# Yamper.net
KiCad netlist of a schematic drawn in Altium Designer
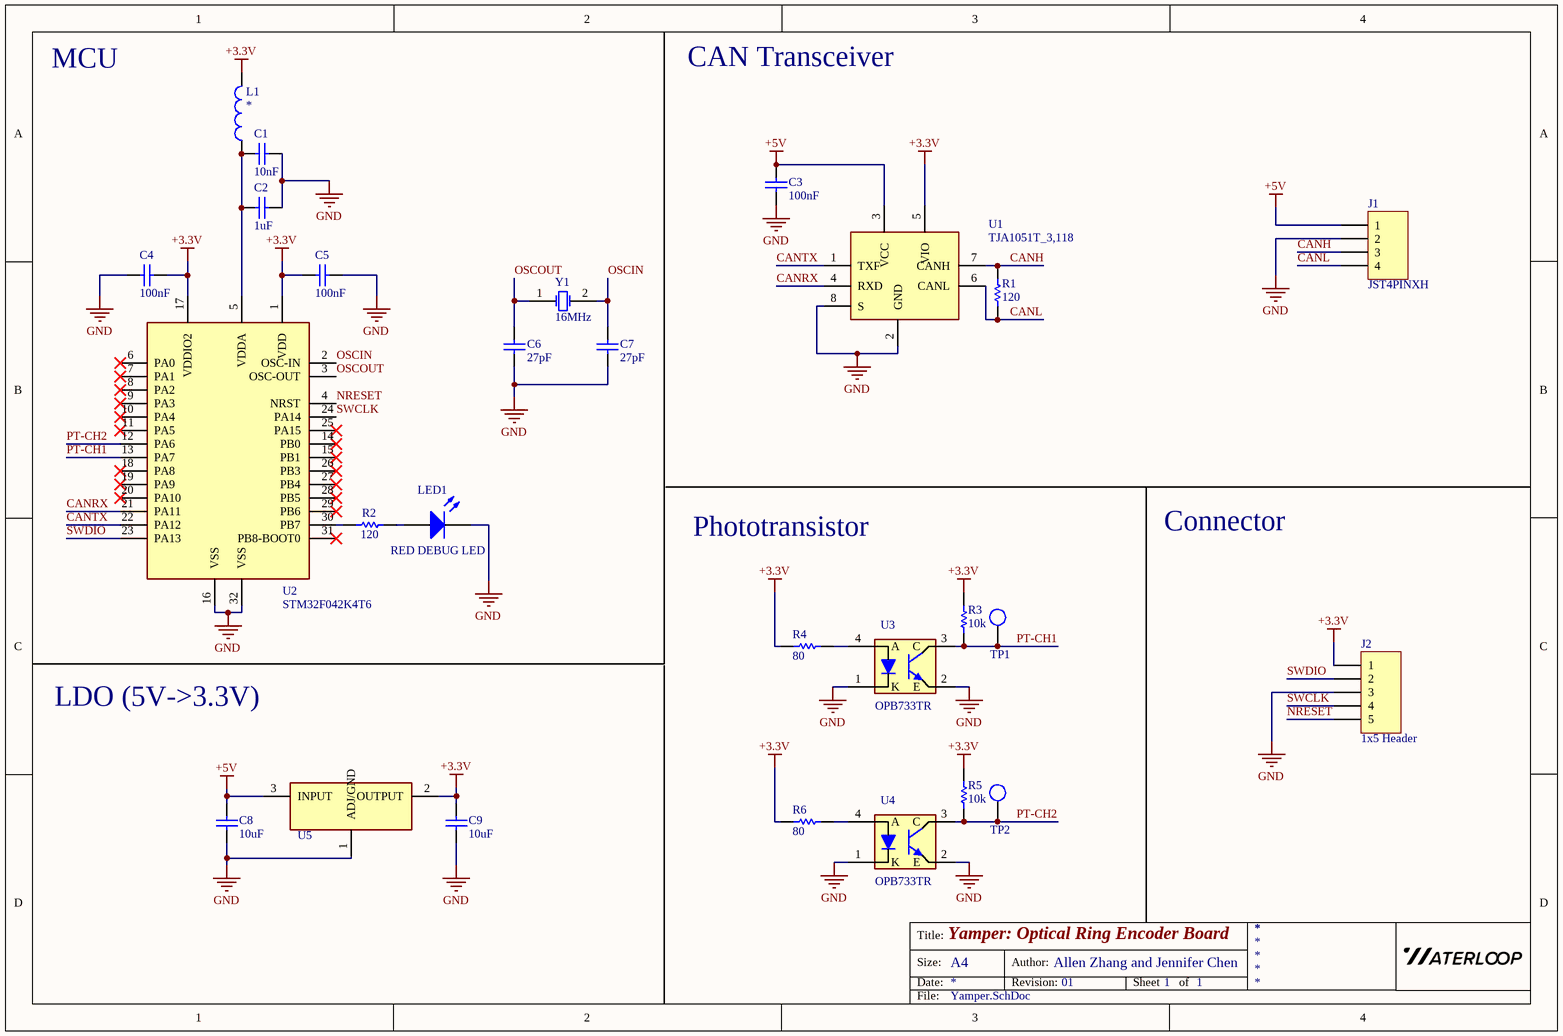
[diagram p0: Yamper.SchDoc]

(export (version "E")
  (design (tool "Eeschema 10.0.6"))
  (components
    (comp (ref "C1")
      (value "10nF")
      (footprint "0805 - Capacitor")
      (description "Nonpolarized Capacitor")
      (fields (field (name "Comment") "Capacitor - Nonpolarized"))
      (libsource (lib "General") (part "Capacitor - Nonpolarized"))
    )
    (comp (ref "C2")
      (value "1uF")
      (footprint "0805 - Capacitor")
      (description "Nonpolarized Capacitor")
      (fields (field (name "Comment") "Capacitor - Nonpolarized"))
      (libsource (lib "General") (part "Capacitor - Nonpolarized"))
    )
    (comp (ref "C3")
      (value "100nF")
      (footprint "0805 - Capacitor")
      (description "Nonpolarized Capacitor")
      (fields (field (name "Comment") "Capacitor - Nonpolarized"))
      (libsource (lib "General") (part "Capacitor - Nonpolarized"))
    )
    (comp (ref "C4")
      (value "100nF")
      (footprint "0805 - Capacitor")
      (description "Nonpolarized Capacitor")
      (fields (field (name "Comment") "Capacitor - Nonpolarized"))
      (libsource (lib "General") (part "Capacitor - Nonpolarized"))
    )
    (comp (ref "C5")
      (value "100nF")
      (footprint "0805 - Capacitor")
      (description "Nonpolarized Capacitor")
      (fields (field (name "Comment") "Capacitor - Nonpolarized"))
      (libsource (lib "General") (part "Capacitor - Nonpolarized"))
    )
    (comp (ref "C6")
      (value "27pF")
      (footprint "0805 - Capacitor")
      (description "Nonpolarized Capacitor")
      (fields (field (name "Comment") "Capacitor - Nonpolarized"))
      (libsource (lib "General") (part "Capacitor - Nonpolarized"))
    )
    (comp (ref "C7")
      (value "27pF")
      (footprint "0805 - Capacitor")
      (description "Nonpolarized Capacitor")
      (fields (field (name "Comment") "Capacitor - Nonpolarized"))
      (libsource (lib "General") (part "Capacitor - Nonpolarized"))
    )
    (comp (ref "C8")
      (value "10uF")
      (footprint "0805 - Capacitor")
      (description "Nonpolarized Capacitor")
      (fields (field (name "Comment") "Capacitor - Nonpolarized"))
      (libsource (lib "General") (part "Capacitor - Nonpolarized"))
    )
    (comp (ref "C9")
      (value "10uF")
      (footprint "0805 - Capacitor")
      (description "Nonpolarized Capacitor")
      (fields (field (name "Comment") "Capacitor - Nonpolarized"))
      (libsource (lib "General") (part "Capacitor - Nonpolarized"))
    )
    (comp (ref "J1")
      (value "JST4PINXH")
      (footprint "B4B-XH")
      (description "1x4 Pin Header")
      (libsource (lib "GeneralConnectors") (part "1x4 Header"))
    )
    (comp (ref "J2")
      (value "1x5 Header")
      (footprint "HDR1X5")
      (description "1x5 Pin Header")
      (libsource (lib "GeneralConnectors") (part "1x5 Header"))
    )
    (comp (ref "L1")
      (value "Inductor")
      (footprint "0805 - Capacitor")
      (fields (field (name "ALTIUM_VALUE") "*"))
      (libsource (lib "General") (part "Inductor"))
    )
    (comp (ref "LED1")
      (value "RED DEBUG LED")
      (footprint "0805 - Resistor")
      (description "Light Emitting Diode")
      (libsource (lib "General") (part "LED"))
    )
    (comp (ref "R1")
      (value "120")
      (footprint "0603 - Resistor")
      (description "Resistor")
      (libsource (lib "General") (part "Resistor"))
    )
    (comp (ref "R2")
      (value "120")
      (footprint "0603 - Resistor")
      (description "Resistor")
      (libsource (lib "General") (part "Resistor"))
    )
    (comp (ref "R3")
      (value "10k")
      (footprint "0603 - Resistor")
      (description "Resistor")
      (libsource (lib "General") (part "Resistor"))
    )
    (comp (ref "R4")
      (value "80")
      (footprint "0603 - Resistor")
      (description "Resistor")
      (libsource (lib "General") (part "Resistor"))
    )
    (comp (ref "R5")
      (value "10k")
      (footprint "0603 - Resistor")
      (description "Resistor")
      (libsource (lib "General") (part "Resistor"))
    )
    (comp (ref "R6")
      (value "80")
      (footprint "0603 - Resistor")
      (description "Resistor")
      (libsource (lib "General") (part "Resistor"))
    )
    (comp (ref "TP1")
      (value "Test Point")
      (footprint "Test Point")
      (libsource (lib "General") (part "Test Point"))
    )
    (comp (ref "TP2")
      (value "Test Point")
      (footprint "Test Point")
      (libsource (lib "General") (part "Test Point"))
    )
    (comp (ref "U1")
      (value "TJA1051T_3,118")
      (footprint "TJA1051T/3,118")
      (description "CAN Transceiver IC 4.5V-5.5V 250ns")
      (fields (field (name "MANUFACTURER") "NXP") (field (name "MANUFACTURER PART NUMBER") "TJA1051T/3,118"))
      (libsource (lib "GeneralComponents") (part "TJA1051T_3,118"))
    )
    (comp (ref "U2")
      (value "STM32F042K4T6")
      (footprint "QFP80P900X900X160-32N")
      (description "Microcontroller")
      (fields (field (name "MOUSER PART NUMBER") "511-STM32F042K4T6"))
      (libsource (lib "Embedded") (part "STM32F042K4T6"))
    )
    (comp (ref "U3")
      (value "OPB733TR")
      (footprint "OPB733TR")
      (description "Phototransistor")
      (libsource (lib "Embedded") (part "OPB733TR"))
    )
    (comp (ref "U4")
      (value "OPB733TR")
      (footprint "OPB733TR")
      (description "Phototransistor")
      (libsource (lib "Embedded") (part "OPB733TR"))
    )
    (comp (ref "U5")
      (value "TLV1117-33IDCYR")
      (footprint "TLV1117")
      (description "Linear Voltage Regulator IC 3.3V 800MA SOT223-4")
      (fields (field (name "MANUFACTURER") "Texas Instruments"))
      (libsource (lib "GeneralComponents") (part "TLV1117-33IDCYR"))
    )
    (comp (ref "Y1")
      (value "16MHz")
      (footprint "2-SMD NO LEAD CRSYSTAL")
      (description "Crystal Oscillator")
      (fields (field (name "Comment") "Oscillator"))
      (libsource (lib "General") (part "Oscillator"))
    )
  )
  (nets
    (net (code "1") (name "+3.3V") (class "Default")
      (node (ref "C4") (pin "1") (pinfunction "1_1") (pintype "passive"))
      (node (ref "C5") (pin "2") (pinfunction "2_2") (pintype "passive"))
      (node (ref "C9") (pin "2") (pinfunction "2_2") (pintype "passive"))
      (node (ref "J2") (pin "1") (pinfunction "1_1") (pintype "passive"))
      (node (ref "L1") (pin "2") (pinfunction "2_2") (pintype "passive"))
      (node (ref "R3") (pin "2") (pinfunction "2_2") (pintype "passive"))
      (node (ref "R4") (pin "1") (pinfunction "1_1") (pintype "passive"))
      (node (ref "R5") (pin "2") (pinfunction "2_2") (pintype "passive"))
      (node (ref "R6") (pin "1") (pinfunction "1_1") (pintype "passive"))
      (node (ref "U1") (pin "5") (pinfunction "VIO_5") (pintype "passive"))
      (node (ref "U2") (pin "1") (pinfunction "VDD_1") (pintype "passive"))
      (node (ref "U2") (pin "17") (pinfunction "VDDIO2_17") (pintype "passive"))
      (node (ref "U5") (pin "2") (pinfunction "OUTPUT_2") (pintype "passive"))
    )
    (net (code "2") (name "+5V") (class "Default")
      (node (ref "C3") (pin "2") (pinfunction "2_2") (pintype "passive"))
      (node (ref "C8") (pin "1") (pinfunction "1_1") (pintype "passive"))
      (node (ref "J1") (pin "1") (pinfunction "1_1") (pintype "passive"))
      (node (ref "U1") (pin "3") (pinfunction "VCC_3") (pintype "passive"))
      (node (ref "U5") (pin "3") (pinfunction "INPUT_3") (pintype "passive"))
    )
    (net (code "3") (name "/CANH") (class "Default")
      (node (ref "J1") (pin "3") (pinfunction "3_3") (pintype "passive"))
      (node (ref "R1") (pin "2") (pinfunction "2_2") (pintype "passive"))
      (node (ref "U1") (pin "7") (pinfunction "CANH_7") (pintype "passive"))
    )
    (net (code "4") (name "/CANL") (class "Default")
      (node (ref "J1") (pin "4") (pinfunction "4_4") (pintype "passive"))
      (node (ref "R1") (pin "1") (pinfunction "1_1") (pintype "passive"))
      (node (ref "U1") (pin "6") (pinfunction "CANL_6") (pintype "passive"))
    )
    (net (code "5") (name "/CANRX") (class "Default")
      (node (ref "U1") (pin "4") (pinfunction "RXD_4") (pintype "passive"))
      (node (ref "U2") (pin "21") (pinfunction "PA11_21") (pintype "passive"))
    )
    (net (code "6") (name "/CANTX") (class "Default")
      (node (ref "U1") (pin "1") (pinfunction "TXF_1") (pintype "passive"))
      (node (ref "U2") (pin "22") (pinfunction "PA12_22") (pintype "passive"))
    )
    (net (code "7") (name "/NRESET") (class "Default")
      (node (ref "J2") (pin "5") (pinfunction "5_5") (pintype "passive"))
      (node (ref "U2") (pin "4") (pinfunction "NRST_4") (pintype "passive"))
    )
    (net (code "8") (name "/OSCIN") (class "Default")
      (node (ref "C7") (pin "2") (pinfunction "2_2") (pintype "passive"))
      (node (ref "U2") (pin "2") (pinfunction "OSC-IN_2") (pintype "passive"))
      (node (ref "Y1") (pin "2") (pinfunction "OSC2_2") (pintype "passive"))
    )
    (net (code "9") (name "/OSCOUT") (class "Default")
      (node (ref "C6") (pin "2") (pinfunction "2_2") (pintype "passive"))
      (node (ref "U2") (pin "3") (pinfunction "OSC-OUT_3") (pintype "passive"))
      (node (ref "Y1") (pin "1") (pinfunction "OSC1_1") (pintype "passive"))
    )
    (net (code "10") (name "/PT-CH1") (class "Default")
      (node (ref "R3") (pin "1") (pinfunction "1_1") (pintype "passive"))
      (node (ref "TP1") (pin "1") (pinfunction "0_1") (pintype "passive"))
      (node (ref "U2") (pin "13") (pinfunction "PA7_13") (pintype "passive"))
      (node (ref "U3") (pin "3") (pinfunction "C_3") (pintype "passive"))
    )
    (net (code "11") (name "/PT-CH2") (class "Default")
      (node (ref "R5") (pin "1") (pinfunction "1_1") (pintype "passive"))
      (node (ref "TP2") (pin "1") (pinfunction "0_1") (pintype "passive"))
      (node (ref "U2") (pin "12") (pinfunction "PA6_12") (pintype "passive"))
      (node (ref "U4") (pin "3") (pinfunction "C_3") (pintype "passive"))
    )
    (net (code "12") (name "/SWCLK") (class "Default")
      (node (ref "J2") (pin "4") (pinfunction "4_4") (pintype "passive"))
      (node (ref "U2") (pin "24") (pinfunction "PA14_24") (pintype "passive"))
    )
    (net (code "13") (name "/SWDIO") (class "Default")
      (node (ref "J2") (pin "2") (pinfunction "2_2") (pintype "passive"))
      (node (ref "U2") (pin "23") (pinfunction "PA13_23") (pintype "passive"))
    )
    (net (code "14") (name "GND") (class "Default")
      (node (ref "C1") (pin "2") (pinfunction "2_2") (pintype "passive"))
      (node (ref "C2") (pin "2") (pinfunction "2_2") (pintype "passive"))
      (node (ref "C3") (pin "1") (pinfunction "1_1") (pintype "passive"))
      (node (ref "C4") (pin "2") (pinfunction "2_2") (pintype "passive"))
      (node (ref "C5") (pin "1") (pinfunction "1_1") (pintype "passive"))
      (node (ref "C6") (pin "1") (pinfunction "1_1") (pintype "passive"))
      (node (ref "C7") (pin "1") (pinfunction "1_1") (pintype "passive"))
      (node (ref "C8") (pin "2") (pinfunction "2_2") (pintype "passive"))
      (node (ref "C9") (pin "1") (pinfunction "1_1") (pintype "passive"))
      (node (ref "J1") (pin "2") (pinfunction "2_2") (pintype "passive"))
      (node (ref "J2") (pin "3") (pinfunction "3_3") (pintype "passive"))
      (node (ref "LED1") (pin "2") (pinfunction "K_2") (pintype "passive"))
      (node (ref "U1") (pin "2") (pinfunction "GND_2") (pintype "passive"))
      (node (ref "U1") (pin "8") (pinfunction "S_8") (pintype "passive"))
      (node (ref "U2") (pin "16") (pinfunction "VSS_16") (pintype "passive"))
      (node (ref "U2") (pin "32") (pinfunction "VSS_32") (pintype "passive"))
      (node (ref "U3") (pin "1") (pinfunction "___K_1") (pintype "passive"))
      (node (ref "U3") (pin "2") (pinfunction "E_2") (pintype "passive"))
      (node (ref "U4") (pin "1") (pinfunction "___K_1") (pintype "passive"))
      (node (ref "U4") (pin "2") (pinfunction "E_2") (pintype "passive"))
      (node (ref "U5") (pin "1") (pinfunction "ADJ/GND_1") (pintype "passive"))
    )
    (net (code "15") (name "Net-(LED1-A)") (class "Default")
      (node (ref "LED1") (pin "1") (pinfunction "A_1") (pintype "passive"))
      (node (ref "R2") (pin "2") (pinfunction "2_2") (pintype "passive"))
    )
    (net (code "16") (name "Net-(U2-PB7)") (class "Default")
      (node (ref "R2") (pin "1") (pinfunction "1_1") (pintype "passive"))
      (node (ref "U2") (pin "30") (pinfunction "PB7_30") (pintype "passive"))
    )
    (net (code "17") (name "Net-(U2-VDDA)") (class "Default")
      (node (ref "C1") (pin "1") (pinfunction "1_1") (pintype "passive"))
      (node (ref "C2") (pin "1") (pinfunction "1_1") (pintype "passive"))
      (node (ref "L1") (pin "1") (pinfunction "1_1") (pintype "passive"))
      (node (ref "U2") (pin "5") (pinfunction "VDDA_5") (pintype "passive"))
    )
    (net (code "18") (name "Net-(U3-___A)") (class "Default")
      (node (ref "R4") (pin "2") (pinfunction "2_2") (pintype "passive"))
      (node (ref "U3") (pin "4") (pinfunction "___A_4") (pintype "passive"))
    )
    (net (code "19") (name "Net-(U4-___A)") (class "Default")
      (node (ref "R6") (pin "2") (pinfunction "2_2") (pintype "passive"))
      (node (ref "U4") (pin "4") (pinfunction "___A_4") (pintype "passive"))
    )
    (net (code "20") (name "unconnected-(U2-PA0-Pad6)") (class "Default")
      (node (ref "U2") (pin "6") (pinfunction "PA0_6") (pintype "passive+no_connect"))
    )
    (net (code "21") (name "unconnected-(U2-PA1-Pad7)") (class "Default")
      (node (ref "U2") (pin "7") (pinfunction "PA1_7") (pintype "passive+no_connect"))
    )
    (net (code "22") (name "unconnected-(U2-PA2-Pad8)") (class "Default")
      (node (ref "U2") (pin "8") (pinfunction "PA2_8") (pintype "passive+no_connect"))
    )
    (net (code "23") (name "unconnected-(U2-PA3-Pad9)") (class "Default")
      (node (ref "U2") (pin "9") (pinfunction "PA3_9") (pintype "passive+no_connect"))
    )
    (net (code "24") (name "unconnected-(U2-PA4-Pad10)") (class "Default")
      (node (ref "U2") (pin "10") (pinfunction "PA4_10") (pintype "passive+no_connect"))
    )
    (net (code "25") (name "unconnected-(U2-PA5-Pad11)") (class "Default")
      (node (ref "U2") (pin "11") (pinfunction "PA5_11") (pintype "passive+no_connect"))
    )
    (net (code "26") (name "unconnected-(U2-PA8-Pad18)") (class "Default")
      (node (ref "U2") (pin "18") (pinfunction "PA8_18") (pintype "passive+no_connect"))
    )
    (net (code "27") (name "unconnected-(U2-PA9-Pad19)") (class "Default")
      (node (ref "U2") (pin "19") (pinfunction "PA9_19") (pintype "passive+no_connect"))
    )
    (net (code "28") (name "unconnected-(U2-PA10-Pad20)") (class "Default")
      (node (ref "U2") (pin "20") (pinfunction "PA10_20") (pintype "passive+no_connect"))
    )
    (net (code "29") (name "unconnected-(U2-PA15-Pad25)") (class "Default")
      (node (ref "U2") (pin "25") (pinfunction "PA15_25") (pintype "passive+no_connect"))
    )
    (net (code "30") (name "unconnected-(U2-PB0-Pad14)") (class "Default")
      (node (ref "U2") (pin "14") (pinfunction "PB0_14") (pintype "passive+no_connect"))
    )
    (net (code "31") (name "unconnected-(U2-PB1-Pad15)") (class "Default")
      (node (ref "U2") (pin "15") (pinfunction "PB1_15") (pintype "passive+no_connect"))
    )
    (net (code "32") (name "unconnected-(U2-PB3-Pad26)") (class "Default")
      (node (ref "U2") (pin "26") (pinfunction "PB3_26") (pintype "passive+no_connect"))
    )
    (net (code "33") (name "unconnected-(U2-PB4-Pad27)") (class "Default")
      (node (ref "U2") (pin "27") (pinfunction "PB4_27") (pintype "passive+no_connect"))
    )
    (net (code "34") (name "unconnected-(U2-PB5-Pad28)") (class "Default")
      (node (ref "U2") (pin "28") (pinfunction "PB5_28") (pintype "passive+no_connect"))
    )
    (net (code "35") (name "unconnected-(U2-PB6-Pad29)") (class "Default")
      (node (ref "U2") (pin "29") (pinfunction "PB6_29") (pintype "passive+no_connect"))
    )
    (net (code "36") (name "unconnected-(U2-PB8-BOOT0-Pad31)") (class "Default")
      (node (ref "U2") (pin "31") (pinfunction "PB8-BOOT0_31") (pintype "passive+no_connect"))
    )
  )
)
